# LCD_Glass_Ext_connector.net
KiCad netlist of a schematic drawn in Altium Designer
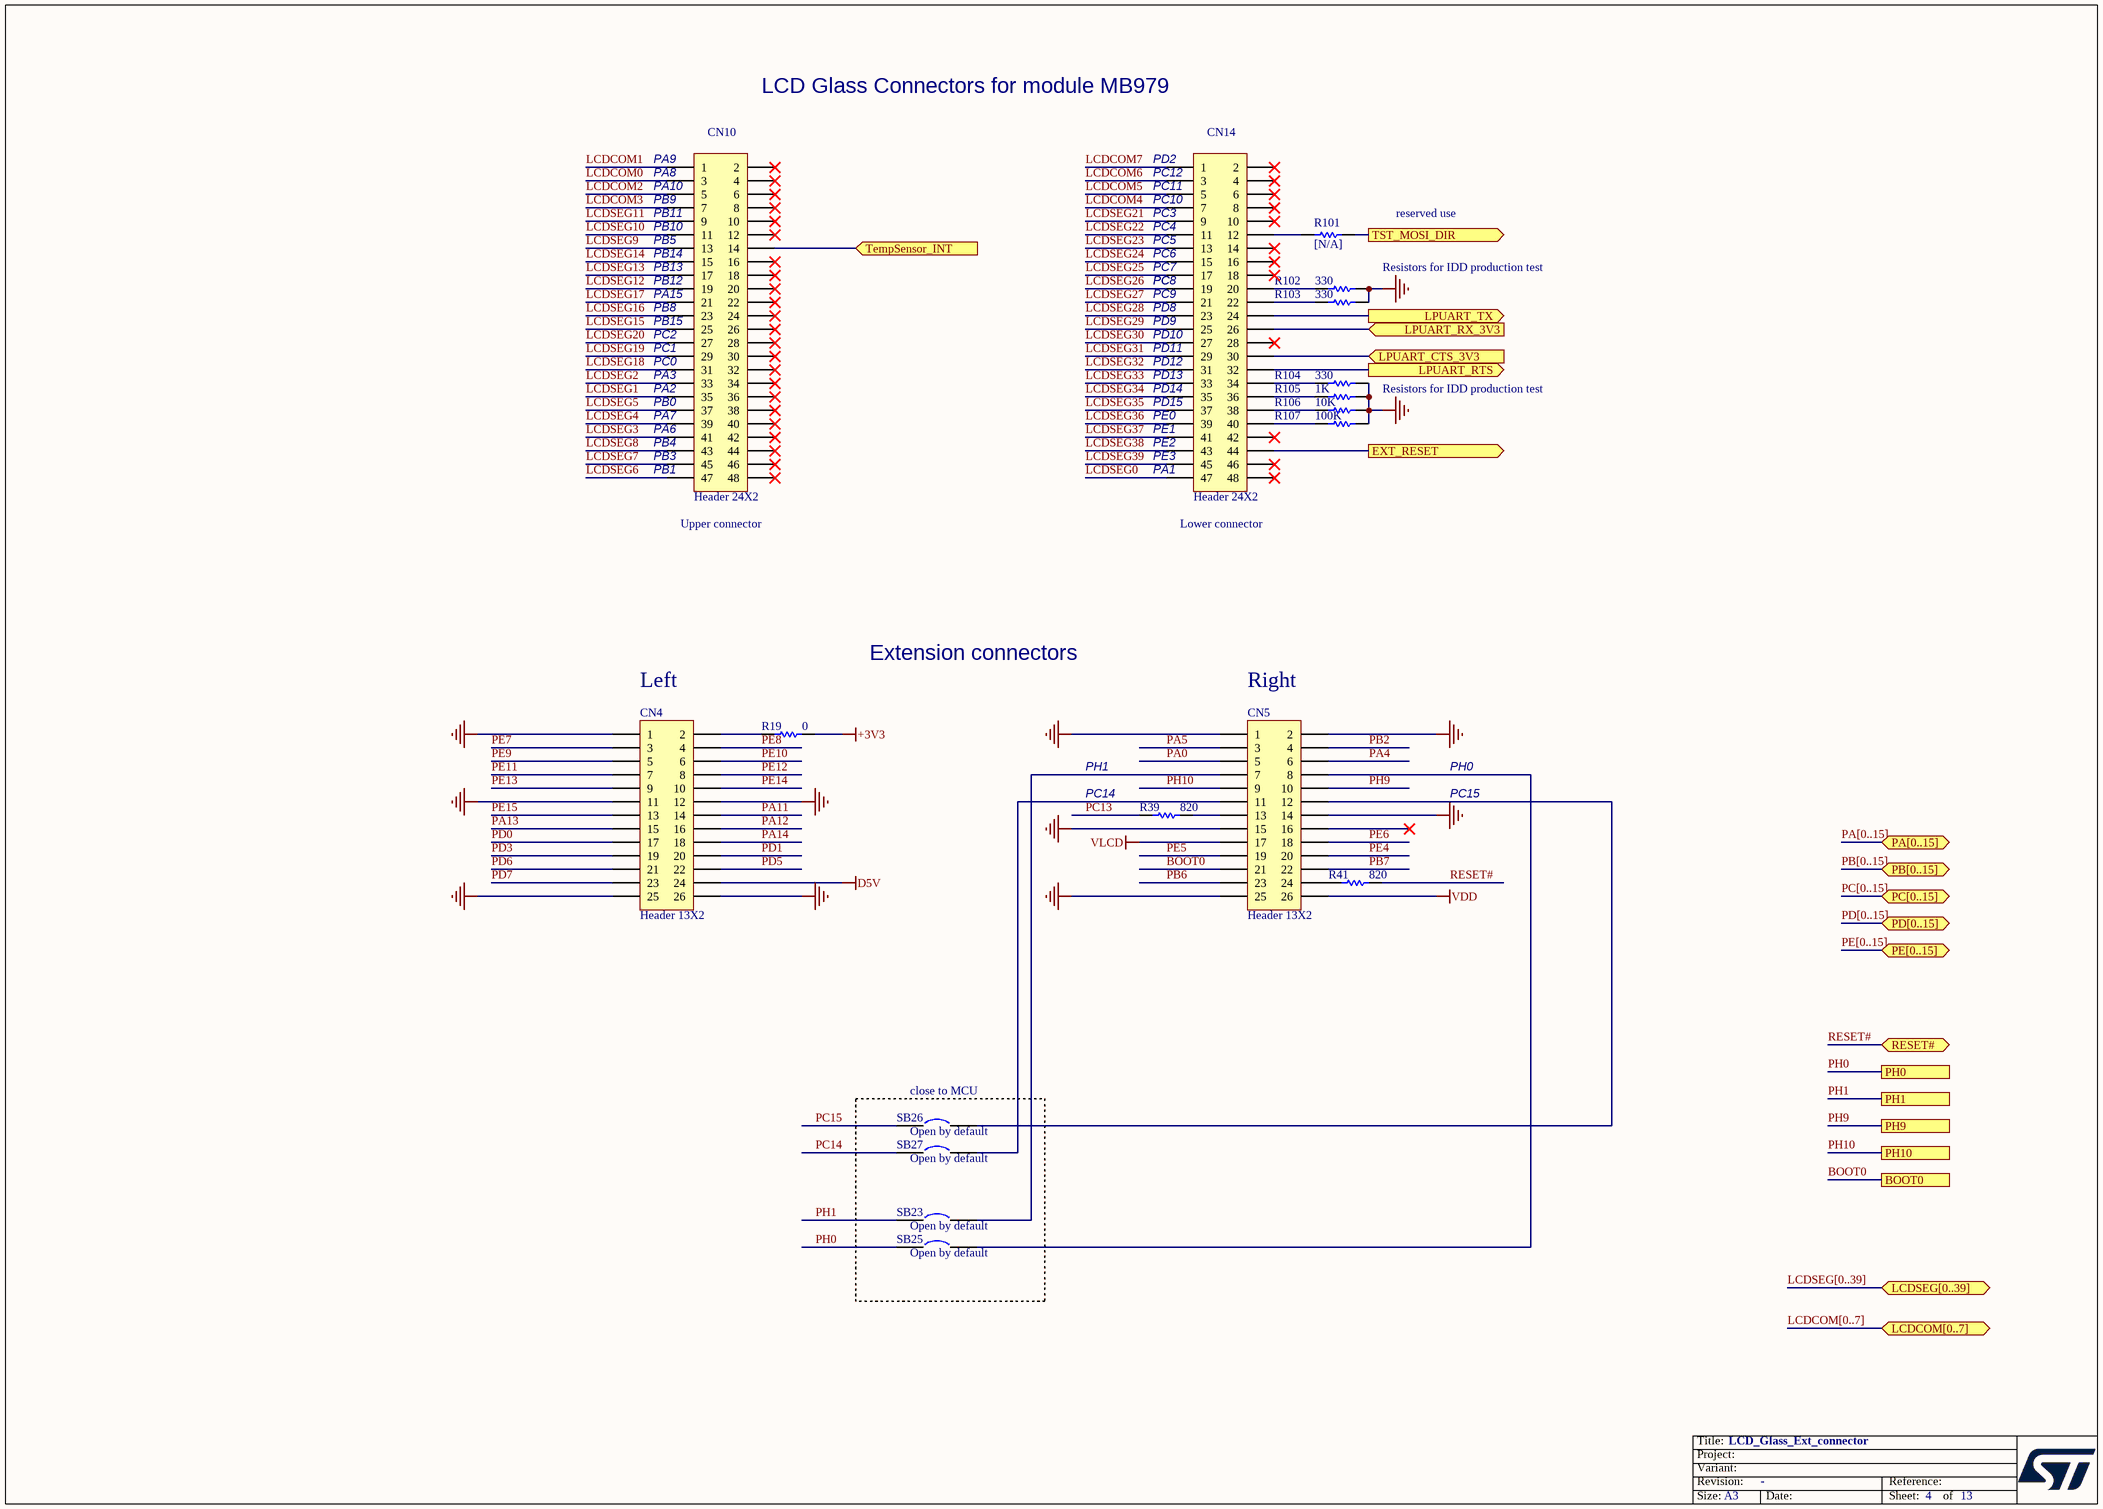
[diagram p0: LCD_Glass_Ext_connector.SchDoc]

(export (version "E")
  (design (tool "Eeschema 10.0.6"))
  (components
    (comp (ref "CN4")
      (value "Header 13X2")
      (footprint "HDR_2X13_2R54")
      (description "Header, 13-Pin, Dual row")
      (fields (field (name "PUBLISHER") "Altium Limited"))
      (libsource (lib "Miscellaneous Connectors") (part "Header 13X2"))
    )
    (comp (ref "CN5")
      (value "Header 13X2")
      (footprint "HDR_2X13_2R54")
      (description "Header, 13-Pin, Dual row")
      (fields (field (name "PUBLISHER") "Altium Limited"))
      (libsource (lib "Miscellaneous Connectors") (part "Header 13X2"))
    )
    (comp (ref "CN10")
      (value "Header 24X2")
      (footprint "HDR_2X24_2R54")
      (description "Header, 24-Pin, Dual row")
      (fields (field (name "PUBLISHER") "Altium Limited"))
      (libsource (lib "Miscellaneous Connectors") (part "Header 24X2"))
    )
    (comp (ref "CN14")
      (value "Header 24X2")
      (footprint "HDR_2X24_2R54")
      (description "Header, 24-Pin, Dual row")
      (fields (field (name "PUBLISHER") "Altium Limited"))
      (libsource (lib "Miscellaneous Connectors") (part "Header 24X2"))
    )
    (comp (ref "R19")
      (value "0")
      (footprint "0603R")
      (description "Resistor")
      (fields (field (name "PUBLISHER") "Altium Limited"))
      (libsource (lib "Miscellaneous Devices") (part "Res1"))
    )
    (comp (ref "R39")
      (value "820")
      (footprint "0603R")
      (description "Resistor")
      (fields (field (name "PUBLISHER") "Altium Limited"))
      (libsource (lib "Miscellaneous Devices") (part "Res1"))
    )
    (comp (ref "R41")
      (value "820")
      (footprint "0603R")
      (description "Resistor")
      (fields (field (name "PUBLISHER") "Altium Limited"))
      (libsource (lib "Miscellaneous Devices") (part "Res1"))
    )
    (comp (ref "R101")
      (value "[N/A]")
      (footprint "0603R")
      (description "Resistor")
      (fields (field (name "PUBLISHER") "Altium Limited"))
      (libsource (lib "Miscellaneous Devices") (part "res1"))
    )
    (comp (ref "R102")
      (value "330")
      (footprint "0603R")
      (description "Resistor")
      (fields (field (name "PUBLISHER") "Altium Limited"))
      (libsource (lib "Miscellaneous Devices") (part "res1"))
    )
    (comp (ref "R103")
      (value "330")
      (footprint "0603R")
      (description "Resistor")
      (fields (field (name "PUBLISHER") "Altium Limited"))
      (libsource (lib "Miscellaneous Devices") (part "res1"))
    )
    (comp (ref "R104")
      (value "330")
      (footprint "0603R")
      (description "Resistor")
      (fields (field (name "PUBLISHER") "Altium Limited"))
      (libsource (lib "Miscellaneous Devices") (part "res1"))
    )
    (comp (ref "R105")
      (value "1K")
      (footprint "0402R")
      (description "Resistor")
      (fields (field (name "PUBLISHER") "Altium Limited"))
      (libsource (lib "Miscellaneous Devices") (part "Res1"))
    )
    (comp (ref "R106")
      (value "10K")
      (footprint "0603R")
      (description "Resistor")
      (fields (field (name "PUBLISHER") "Altium Limited"))
      (libsource (lib "Miscellaneous Devices") (part "res1"))
    )
    (comp (ref "R107")
      (value "100K")
      (footprint "0603R")
      (description "Resistor")
      (fields (field (name "PUBLISHER") "Altium Limited"))
      (libsource (lib "Miscellaneous Devices") (part "res1"))
    )
    (comp (ref "SB23")
      (value "Open by default")
      (footprint "SB_0603")
      (description "Circuit Breaker")
      (fields (field (name "PUBLISHER") "Altium Limited"))
      (libsource (lib "Miscellaneous Devices") (part "Circuit Breaker"))
    )
    (comp (ref "SB25")
      (value "Open by default")
      (footprint "SB_0603")
      (description "Circuit Breaker")
      (fields (field (name "PUBLISHER") "Altium Limited"))
      (libsource (lib "Miscellaneous Devices") (part "Circuit Breaker"))
    )
    (comp (ref "SB26")
      (value "Open by default")
      (footprint "SB_0603")
      (description "Circuit Breaker")
      (fields (field (name "PUBLISHER") "Altium Limited"))
      (libsource (lib "Miscellaneous Devices") (part "Circuit Breaker"))
    )
    (comp (ref "SB27")
      (value "Open by default")
      (footprint "SB_0603")
      (description "Circuit Breaker")
      (fields (field (name "PUBLISHER") "Altium Limited"))
      (libsource (lib "Miscellaneous Devices") (part "Circuit Breaker"))
    )
  )
  (nets
    (net (code "50") (name "+3V3") (class "Default")
      (node (ref "R19") (pin "1") (pinfunction "1_1") (pintype "passive"))
    )
    (net (code "51") (name "/BOOT0") (class "Default")
      (node (ref "CN5") (pin "21") (pinfunction "21_21") (pintype "passive"))
    )
    (net (code "52") (name "/EXT_RESET") (class "Default")
      (node (ref "CN14") (pin "44") (pinfunction "44_44") (pintype "passive"))
    )
    (net (code "53") (name "/LCDCOM0") (class "Default")
      (node (ref "CN10") (pin "3") (pinfunction "3_3") (pintype "passive"))
    )
    (net (code "54") (name "/LCDCOM1") (class "Default")
      (node (ref "CN10") (pin "1") (pinfunction "1_1") (pintype "passive"))
    )
    (net (code "55") (name "/LCDCOM2") (class "Default")
      (node (ref "CN10") (pin "5") (pinfunction "5_5") (pintype "passive"))
    )
    (net (code "56") (name "/LCDCOM3") (class "Default")
      (node (ref "CN10") (pin "7") (pinfunction "7_7") (pintype "passive"))
    )
    (net (code "57") (name "/LCDCOM4") (class "Default")
      (node (ref "CN14") (pin "7") (pinfunction "7_7") (pintype "passive"))
    )
    (net (code "58") (name "/LCDCOM5") (class "Default")
      (node (ref "CN14") (pin "5") (pinfunction "5_5") (pintype "passive"))
    )
    (net (code "59") (name "/LCDCOM6") (class "Default")
      (node (ref "CN14") (pin "3") (pinfunction "3_3") (pintype "passive"))
    )
    (net (code "60") (name "/LCDCOM7") (class "Default")
      (node (ref "CN14") (pin "1") (pinfunction "1_1") (pintype "passive"))
    )
    (net (code "62") (name "/LCDSEG0") (class "Default")
      (node (ref "CN14") (pin "47") (pinfunction "47_47") (pintype "passive"))
    )
    (net (code "63") (name "/LCDSEG1") (class "Default")
      (node (ref "CN10") (pin "35") (pinfunction "35_35") (pintype "passive"))
    )
    (net (code "64") (name "/LCDSEG2") (class "Default")
      (node (ref "CN10") (pin "33") (pinfunction "33_33") (pintype "passive"))
    )
    (net (code "65") (name "/LCDSEG3") (class "Default")
      (node (ref "CN10") (pin "41") (pinfunction "41_41") (pintype "passive"))
    )
    (net (code "66") (name "/LCDSEG4") (class "Default")
      (node (ref "CN10") (pin "39") (pinfunction "39_39") (pintype "passive"))
    )
    (net (code "67") (name "/LCDSEG5") (class "Default")
      (node (ref "CN10") (pin "37") (pinfunction "37_37") (pintype "passive"))
    )
    (net (code "68") (name "/LCDSEG6") (class "Default")
      (node (ref "CN10") (pin "47") (pinfunction "47_47") (pintype "passive"))
    )
    (net (code "69") (name "/LCDSEG7") (class "Default")
      (node (ref "CN10") (pin "45") (pinfunction "45_45") (pintype "passive"))
    )
    (net (code "70") (name "/LCDSEG8") (class "Default")
      (node (ref "CN10") (pin "43") (pinfunction "43_43") (pintype "passive"))
    )
    (net (code "71") (name "/LCDSEG9") (class "Default")
      (node (ref "CN10") (pin "13") (pinfunction "13_13") (pintype "passive"))
    )
    (net (code "72") (name "/LCDSEG10") (class "Default")
      (node (ref "CN10") (pin "11") (pinfunction "11_11") (pintype "passive"))
    )
    (net (code "73") (name "/LCDSEG11") (class "Default")
      (node (ref "CN10") (pin "9") (pinfunction "9_9") (pintype "passive"))
    )
    (net (code "74") (name "/LCDSEG12") (class "Default")
      (node (ref "CN10") (pin "19") (pinfunction "19_19") (pintype "passive"))
    )
    (net (code "75") (name "/LCDSEG13") (class "Default")
      (node (ref "CN10") (pin "17") (pinfunction "17_17") (pintype "passive"))
    )
    (net (code "76") (name "/LCDSEG14") (class "Default")
      (node (ref "CN10") (pin "15") (pinfunction "15_15") (pintype "passive"))
    )
    (net (code "77") (name "/LCDSEG15") (class "Default")
      (node (ref "CN10") (pin "25") (pinfunction "25_25") (pintype "passive"))
    )
    (net (code "78") (name "/LCDSEG16") (class "Default")
      (node (ref "CN10") (pin "23") (pinfunction "23_23") (pintype "passive"))
    )
    (net (code "79") (name "/LCDSEG17") (class "Default")
      (node (ref "CN10") (pin "21") (pinfunction "21_21") (pintype "passive"))
    )
    (net (code "80") (name "/LCDSEG18") (class "Default")
      (node (ref "CN10") (pin "31") (pinfunction "31_31") (pintype "passive"))
    )
    (net (code "81") (name "/LCDSEG19") (class "Default")
      (node (ref "CN10") (pin "29") (pinfunction "29_29") (pintype "passive"))
    )
    (net (code "82") (name "/LCDSEG20") (class "Default")
      (node (ref "CN10") (pin "27") (pinfunction "27_27") (pintype "passive"))
    )
    (net (code "83") (name "/LCDSEG21") (class "Default")
      (node (ref "CN14") (pin "9") (pinfunction "9_9") (pintype "passive"))
    )
    (net (code "84") (name "/LCDSEG22") (class "Default")
      (node (ref "CN14") (pin "11") (pinfunction "11_11") (pintype "passive"))
    )
    (net (code "85") (name "/LCDSEG23") (class "Default")
      (node (ref "CN14") (pin "13") (pinfunction "13_13") (pintype "passive"))
    )
    (net (code "86") (name "/LCDSEG24") (class "Default")
      (node (ref "CN14") (pin "15") (pinfunction "15_15") (pintype "passive"))
    )
    (net (code "87") (name "/LCDSEG25") (class "Default")
      (node (ref "CN14") (pin "17") (pinfunction "17_17") (pintype "passive"))
    )
    (net (code "88") (name "/LCDSEG26") (class "Default")
      (node (ref "CN14") (pin "19") (pinfunction "19_19") (pintype "passive"))
    )
    (net (code "89") (name "/LCDSEG27") (class "Default")
      (node (ref "CN14") (pin "21") (pinfunction "21_21") (pintype "passive"))
    )
    (net (code "90") (name "/LCDSEG28") (class "Default")
      (node (ref "CN14") (pin "23") (pinfunction "23_23") (pintype "passive"))
    )
    (net (code "91") (name "/LCDSEG29") (class "Default")
      (node (ref "CN14") (pin "25") (pinfunction "25_25") (pintype "passive"))
    )
    (net (code "92") (name "/LCDSEG30") (class "Default")
      (node (ref "CN14") (pin "27") (pinfunction "27_27") (pintype "passive"))
    )
    (net (code "93") (name "/LCDSEG31") (class "Default")
      (node (ref "CN14") (pin "29") (pinfunction "29_29") (pintype "passive"))
    )
    (net (code "94") (name "/LCDSEG32") (class "Default")
      (node (ref "CN14") (pin "31") (pinfunction "31_31") (pintype "passive"))
    )
    (net (code "95") (name "/LCDSEG33") (class "Default")
      (node (ref "CN14") (pin "33") (pinfunction "33_33") (pintype "passive"))
    )
    (net (code "96") (name "/LCDSEG34") (class "Default")
      (node (ref "CN14") (pin "35") (pinfunction "35_35") (pintype "passive"))
    )
    (net (code "97") (name "/LCDSEG35") (class "Default")
      (node (ref "CN14") (pin "37") (pinfunction "37_37") (pintype "passive"))
    )
    (net (code "98") (name "/LCDSEG36") (class "Default")
      (node (ref "CN14") (pin "39") (pinfunction "39_39") (pintype "passive"))
    )
    (net (code "99") (name "/LCDSEG37") (class "Default")
      (node (ref "CN14") (pin "41") (pinfunction "41_41") (pintype "passive"))
    )
    (net (code "100") (name "/LCDSEG38") (class "Default")
      (node (ref "CN14") (pin "43") (pinfunction "43_43") (pintype "passive"))
    )
    (net (code "101") (name "/LCDSEG39") (class "Default")
      (node (ref "CN14") (pin "45") (pinfunction "45_45") (pintype "passive"))
    )
    (net (code "103") (name "/LPUART_CTS_3V3") (class "Default")
      (node (ref "CN14") (pin "30") (pinfunction "30_30") (pintype "passive"))
    )
    (net (code "104") (name "/LPUART_RTS") (class "Default")
      (node (ref "CN14") (pin "32") (pinfunction "32_32") (pintype "passive"))
    )
    (net (code "105") (name "/LPUART_RX_3V3") (class "Default")
      (node (ref "CN14") (pin "26") (pinfunction "26_26") (pintype "passive"))
    )
    (net (code "106") (name "/LPUART_TX") (class "Default")
      (node (ref "CN14") (pin "24") (pinfunction "24_24") (pintype "passive"))
    )
    (net (code "107") (name "/PA0") (class "Default")
      (node (ref "CN5") (pin "5") (pinfunction "5_5") (pintype "passive"))
    )
    (net (code "108") (name "/PA4") (class "Default")
      (node (ref "CN5") (pin "6") (pinfunction "6_6") (pintype "passive"))
    )
    (net (code "109") (name "/PA5") (class "Default")
      (node (ref "CN5") (pin "3") (pinfunction "3_3") (pintype "passive"))
    )
    (net (code "110") (name "/PA11") (class "Default")
      (node (ref "CN4") (pin "14") (pinfunction "14_14") (pintype "passive"))
    )
    (net (code "111") (name "/PA12") (class "Default")
      (node (ref "CN4") (pin "16") (pinfunction "16_16") (pintype "passive"))
    )
    (net (code "112") (name "/PA13") (class "Default")
      (node (ref "CN4") (pin "15") (pinfunction "15_15") (pintype "passive"))
    )
    (net (code "113") (name "/PA14") (class "Default")
      (node (ref "CN4") (pin "18") (pinfunction "18_18") (pintype "passive"))
    )
    (net (code "115") (name "/PB2") (class "Default")
      (node (ref "CN5") (pin "4") (pinfunction "4_4") (pintype "passive"))
    )
    (net (code "116") (name "/PB6") (class "Default")
      (node (ref "CN5") (pin "23") (pinfunction "23_23") (pintype "passive"))
    )
    (net (code "117") (name "/PB7") (class "Default")
      (node (ref "CN5") (pin "22") (pinfunction "22_22") (pintype "passive"))
    )
    (net (code "119") (name "/PC13") (class "Default")
      (node (ref "R39") (pin "1") (pinfunction "1_1") (pintype "passive"))
    )
    (net (code "120") (name "/PC14") (class "Default")
      (node (ref "SB27") (pin "1") (pinfunction "1_1") (pintype "passive"))
    )
    (net (code "121") (name "/PC15") (class "Default")
      (node (ref "SB26") (pin "1") (pinfunction "1_1") (pintype "passive"))
    )
    (net (code "123") (name "/PD0") (class "Default")
      (node (ref "CN4") (pin "17") (pinfunction "17_17") (pintype "passive"))
    )
    (net (code "124") (name "/PD1") (class "Default")
      (node (ref "CN4") (pin "20") (pinfunction "20_20") (pintype "passive"))
    )
    (net (code "125") (name "/PD3") (class "Default")
      (node (ref "CN4") (pin "19") (pinfunction "19_19") (pintype "passive"))
    )
    (net (code "126") (name "/PD5") (class "Default")
      (node (ref "CN4") (pin "22") (pinfunction "22_22") (pintype "passive"))
    )
    (net (code "127") (name "/PD6") (class "Default")
      (node (ref "CN4") (pin "21") (pinfunction "21_21") (pintype "passive"))
    )
    (net (code "128") (name "/PD7") (class "Default")
      (node (ref "CN4") (pin "23") (pinfunction "23_23") (pintype "passive"))
    )
    (net (code "130") (name "/PE4") (class "Default")
      (node (ref "CN5") (pin "20") (pinfunction "20_20") (pintype "passive"))
    )
    (net (code "131") (name "/PE5") (class "Default")
      (node (ref "CN5") (pin "19") (pinfunction "19_19") (pintype "passive"))
    )
    (net (code "132") (name "/PE6") (class "Default")
      (node (ref "CN5") (pin "18") (pinfunction "18_18") (pintype "passive"))
    )
    (net (code "133") (name "/PE7") (class "Default")
      (node (ref "CN4") (pin "3") (pinfunction "3_3") (pintype "passive"))
    )
    (net (code "134") (name "/PE8") (class "Default")
      (node (ref "CN4") (pin "4") (pinfunction "4_4") (pintype "passive"))
    )
    (net (code "135") (name "/PE9") (class "Default")
      (node (ref "CN4") (pin "5") (pinfunction "5_5") (pintype "passive"))
    )
    (net (code "136") (name "/PE10") (class "Default")
      (node (ref "CN4") (pin "6") (pinfunction "6_6") (pintype "passive"))
    )
    (net (code "137") (name "/PE11") (class "Default")
      (node (ref "CN4") (pin "7") (pinfunction "7_7") (pintype "passive"))
    )
    (net (code "138") (name "/PE12") (class "Default")
      (node (ref "CN4") (pin "8") (pinfunction "8_8") (pintype "passive"))
    )
    (net (code "139") (name "/PE13") (class "Default")
      (node (ref "CN4") (pin "9") (pinfunction "9_9") (pintype "passive"))
    )
    (net (code "140") (name "/PE14") (class "Default")
      (node (ref "CN4") (pin "10") (pinfunction "10_10") (pintype "passive"))
    )
    (net (code "141") (name "/PE15") (class "Default")
      (node (ref "CN4") (pin "13") (pinfunction "13_13") (pintype "passive"))
    )
    (net (code "143") (name "/PH0") (class "Default")
      (node (ref "SB25") (pin "1") (pinfunction "1_1") (pintype "passive"))
    )
    (net (code "144") (name "/PH1") (class "Default")
      (node (ref "SB23") (pin "1") (pinfunction "1_1") (pintype "passive"))
    )
    (net (code "145") (name "/PH9") (class "Default")
      (node (ref "CN5") (pin "10") (pinfunction "10_10") (pintype "passive"))
    )
    (net (code "146") (name "/PH10") (class "Default")
      (node (ref "CN5") (pin "9") (pinfunction "9_9") (pintype "passive"))
    )
    (net (code "147") (name "/RESET#") (class "Default")
      (node (ref "R41") (pin "1") (pinfunction "1_1") (pintype "passive"))
    )
    (net (code "148") (name "/TST_MOSI_DIR") (class "Default")
      (node (ref "R101") (pin "1") (pinfunction "1_1") (pintype "passive"))
    )
    (net (code "149") (name "/TempSensor_INT") (class "Default")
      (node (ref "CN10") (pin "14") (pinfunction "14_14") (pintype "passive"))
    )
    (net (code "150") (name "D5V") (class "Default")
      (node (ref "CN4") (pin "24") (pinfunction "24_24") (pintype "passive"))
    )
    (net (code "151") (name "GND") (class "Default")
      (node (ref "CN4") (pin "1") (pinfunction "1_1") (pintype "passive"))
      (node (ref "CN4") (pin "11") (pinfunction "11_11") (pintype "passive"))
      (node (ref "CN4") (pin "12") (pinfunction "12_12") (pintype "passive"))
      (node (ref "CN4") (pin "25") (pinfunction "25_25") (pintype "passive"))
      (node (ref "CN4") (pin "26") (pinfunction "26_26") (pintype "passive"))
      (node (ref "CN5") (pin "1") (pinfunction "1_1") (pintype "passive"))
      (node (ref "CN5") (pin "14") (pinfunction "14_14") (pintype "passive"))
      (node (ref "CN5") (pin "15") (pinfunction "15_15") (pintype "passive"))
      (node (ref "CN5") (pin "2") (pinfunction "2_2") (pintype "passive"))
      (node (ref "CN5") (pin "25") (pinfunction "25_25") (pintype "passive"))
      (node (ref "R102") (pin "1") (pinfunction "1_1") (pintype "passive"))
      (node (ref "R103") (pin "1") (pinfunction "1_1") (pintype "passive"))
      (node (ref "R104") (pin "1") (pinfunction "1_1") (pintype "passive"))
      (node (ref "R105") (pin "2") (pinfunction "2_2") (pintype "passive"))
      (node (ref "R106") (pin "1") (pinfunction "1_1") (pintype "passive"))
      (node (ref "R107") (pin "1") (pinfunction "1_1") (pintype "passive"))
    )
    (net (code "152") (name "Net-(CN4-Pad2)") (class "Default")
      (node (ref "CN4") (pin "2") (pinfunction "2_2") (pintype "passive"))
      (node (ref "R19") (pin "2") (pinfunction "2_2") (pintype "passive"))
    )
    (net (code "153") (name "Net-(CN5-Pad7)") (class "Default")
      (node (ref "CN5") (pin "7") (pinfunction "7_7") (pintype "passive"))
      (node (ref "SB23") (pin "2") (pinfunction "2_2") (pintype "passive"))
    )
    (net (code "154") (name "Net-(CN5-Pad8)") (class "Default")
      (node (ref "CN5") (pin "8") (pinfunction "8_8") (pintype "passive"))
      (node (ref "SB25") (pin "2") (pinfunction "2_2") (pintype "passive"))
    )
    (net (code "155") (name "Net-(CN5-Pad11)") (class "Default")
      (node (ref "CN5") (pin "11") (pinfunction "11_11") (pintype "passive"))
      (node (ref "SB27") (pin "2") (pinfunction "2_2") (pintype "passive"))
    )
    (net (code "156") (name "Net-(CN5-Pad12)") (class "Default")
      (node (ref "CN5") (pin "12") (pinfunction "12_12") (pintype "passive"))
      (node (ref "SB26") (pin "2") (pinfunction "2_2") (pintype "passive"))
    )
    (net (code "157") (name "Net-(CN5-Pad13)") (class "Default")
      (node (ref "CN5") (pin "13") (pinfunction "13_13") (pintype "passive"))
      (node (ref "R39") (pin "2") (pinfunction "2_2") (pintype "passive"))
    )
    (net (code "158") (name "Net-(CN5-Pad24)") (class "Default")
      (node (ref "CN5") (pin "24") (pinfunction "24_24") (pintype "passive"))
      (node (ref "R41") (pin "2") (pinfunction "2_2") (pintype "passive"))
    )
    (net (code "159") (name "Net-(CN14-Pad12)") (class "Default")
      (node (ref "CN14") (pin "12") (pinfunction "12_12") (pintype "passive"))
      (node (ref "R101") (pin "2") (pinfunction "2_2") (pintype "passive"))
    )
    (net (code "160") (name "Net-(CN14-Pad20)") (class "Default")
      (node (ref "CN14") (pin "20") (pinfunction "20_20") (pintype "passive"))
      (node (ref "R102") (pin "2") (pinfunction "2_2") (pintype "passive"))
    )
    (net (code "161") (name "Net-(CN14-Pad22)") (class "Default")
      (node (ref "CN14") (pin "22") (pinfunction "22_22") (pintype "passive"))
      (node (ref "R103") (pin "2") (pinfunction "2_2") (pintype "passive"))
    )
    (net (code "162") (name "Net-(CN14-Pad34)") (class "Default")
      (node (ref "CN14") (pin "34") (pinfunction "34_34") (pintype "passive"))
      (node (ref "R104") (pin "2") (pinfunction "2_2") (pintype "passive"))
    )
    (net (code "163") (name "Net-(CN14-Pad36)") (class "Default")
      (node (ref "CN14") (pin "36") (pinfunction "36_36") (pintype "passive"))
      (node (ref "R105") (pin "1") (pinfunction "1_1") (pintype "passive"))
    )
    (net (code "164") (name "Net-(CN14-Pad38)") (class "Default")
      (node (ref "CN14") (pin "38") (pinfunction "38_38") (pintype "passive"))
      (node (ref "R106") (pin "2") (pinfunction "2_2") (pintype "passive"))
    )
    (net (code "165") (name "Net-(CN14-Pad40)") (class "Default")
      (node (ref "CN14") (pin "40") (pinfunction "40_40") (pintype "passive"))
      (node (ref "R107") (pin "2") (pinfunction "2_2") (pintype "passive"))
    )
    (net (code "166") (name "VDD") (class "Default")
      (node (ref "CN5") (pin "26") (pinfunction "26_26") (pintype "passive"))
    )
    (net (code "167") (name "VLCD") (class "Default")
      (node (ref "CN5") (pin "17") (pinfunction "17_17") (pintype "passive"))
    )
    (net (code "168") (name "unconnected-(CN5-Pad16)") (class "Default")
      (node (ref "CN5") (pin "16") (pinfunction "16_16") (pintype "passive+no_connect"))
    )
    (net (code "169") (name "unconnected-(CN10-Pad2)") (class "Default")
      (node (ref "CN10") (pin "2") (pinfunction "2_2") (pintype "passive+no_connect"))
    )
    (net (code "170") (name "unconnected-(CN10-Pad4)") (class "Default")
      (node (ref "CN10") (pin "4") (pinfunction "4_4") (pintype "passive+no_connect"))
    )
    (net (code "171") (name "unconnected-(CN10-Pad6)") (class "Default")
      (node (ref "CN10") (pin "6") (pinfunction "6_6") (pintype "passive+no_connect"))
    )
    (net (code "172") (name "unconnected-(CN10-Pad8)") (class "Default")
      (node (ref "CN10") (pin "8") (pinfunction "8_8") (pintype "passive+no_connect"))
    )
    (net (code "173") (name "unconnected-(CN10-Pad10)") (class "Default")
      (node (ref "CN10") (pin "10") (pinfunction "10_10") (pintype "passive+no_connect"))
    )
    (net (code "174") (name "unconnected-(CN10-Pad12)") (class "Default")
      (node (ref "CN10") (pin "12") (pinfunction "12_12") (pintype "passive+no_connect"))
    )
    (net (code "175") (name "unconnected-(CN10-Pad16)") (class "Default")
      (node (ref "CN10") (pin "16") (pinfunction "16_16") (pintype "passive+no_connect"))
    )
    (net (code "176") (name "unconnected-(CN10-Pad18)") (class "Default")
      (node (ref "CN10") (pin "18") (pinfunction "18_18") (pintype "passive+no_connect"))
    )
    (net (code "177") (name "unconnected-(CN10-Pad20)") (class "Default")
      (node (ref "CN10") (pin "20") (pinfunction "20_20") (pintype "passive+no_connect"))
    )
    (net (code "178") (name "unconnected-(CN10-Pad22)") (class "Default")
      (node (ref "CN10") (pin "22") (pinfunction "22_22") (pintype "passive+no_connect"))
    )
    (net (code "179") (name "unconnected-(CN10-Pad24)") (class "Default")
      (node (ref "CN10") (pin "24") (pinfunction "24_24") (pintype "passive+no_connect"))
    )
    (net (code "180") (name "unconnected-(CN10-Pad26)") (class "Default")
      (node (ref "CN10") (pin "26") (pinfunction "26_26") (pintype "passive+no_connect"))
    )
    (net (code "181") (name "unconnected-(CN10-Pad28)") (class "Default")
      (node (ref "CN10") (pin "28") (pinfunction "28_28") (pintype "passive+no_connect"))
    )
    (net (code "182") (name "unconnected-(CN10-Pad30)") (class "Default")
      (node (ref "CN10") (pin "30") (pinfunction "30_30") (pintype "passive+no_connect"))
    )
    (net (code "183") (name "unconnected-(CN10-Pad32)") (class "Default")
      (node (ref "CN10") (pin "32") (pinfunction "32_32") (pintype "passive+no_connect"))
    )
    (net (code "184") (name "unconnected-(CN10-Pad34)") (class "Default")
      (node (ref "CN10") (pin "34") (pinfunction "34_34") (pintype "passive+no_connect"))
    )
    (net (code "185") (name "unconnected-(CN10-Pad36)") (class "Default")
      (node (ref "CN10") (pin "36") (pinfunction "36_36") (pintype "passive+no_connect"))
    )
    (net (code "186") (name "unconnected-(CN10-Pad38)") (class "Default")
      (node (ref "CN10") (pin "38") (pinfunction "38_38") (pintype "passive+no_connect"))
    )
    (net (code "187") (name "unconnected-(CN10-Pad40)") (class "Default")
      (node (ref "CN10") (pin "40") (pinfunction "40_40") (pintype "passive+no_connect"))
    )
    (net (code "188") (name "unconnected-(CN10-Pad42)") (class "Default")
      (node (ref "CN10") (pin "42") (pinfunction "42_42") (pintype "passive+no_connect"))
    )
    (net (code "189") (name "unconnected-(CN10-Pad44)") (class "Default")
      (node (ref "CN10") (pin "44") (pinfunction "44_44") (pintype "passive+no_connect"))
    )
    (net (code "190") (name "unconnected-(CN10-Pad46)") (class "Default")
      (node (ref "CN10") (pin "46") (pinfunction "46_46") (pintype "passive+no_connect"))
    )
    (net (code "191") (name "unconnected-(CN10-Pad48)") (class "Default")
      (node (ref "CN10") (pin "48") (pinfunction "48_48") (pintype "passive+no_connect"))
    )
    (net (code "192") (name "unconnected-(CN14-Pad2)") (class "Default")
      (node (ref "CN14") (pin "2") (pinfunction "2_2") (pintype "passive+no_connect"))
    )
    (net (code "193") (name "unconnected-(CN14-Pad4)") (class "Default")
      (node (ref "CN14") (pin "4") (pinfunction "4_4") (pintype "passive+no_connect"))
    )
    (net (code "194") (name "unconnected-(CN14-Pad6)") (class "Default")
      (node (ref "CN14") (pin "6") (pinfunction "6_6") (pintype "passive+no_connect"))
    )
    (net (code "195") (name "unconnected-(CN14-Pad8)") (class "Default")
      (node (ref "CN14") (pin "8") (pinfunction "8_8") (pintype "passive+no_connect"))
    )
    (net (code "196") (name "unconnected-(CN14-Pad10)") (class "Default")
      (node (ref "CN14") (pin "10") (pinfunction "10_10") (pintype "passive+no_connect"))
    )
    (net (code "197") (name "unconnected-(CN14-Pad14)") (class "Default")
      (node (ref "CN14") (pin "14") (pinfunction "14_14") (pintype "passive+no_connect"))
    )
    (net (code "198") (name "unconnected-(CN14-Pad16)") (class "Default")
      (node (ref "CN14") (pin "16") (pinfunction "16_16") (pintype "passive+no_connect"))
    )
    (net (code "199") (name "unconnected-(CN14-Pad18)") (class "Default")
      (node (ref "CN14") (pin "18") (pinfunction "18_18") (pintype "passive+no_connect"))
    )
    (net (code "200") (name "unconnected-(CN14-Pad28)") (class "Default")
      (node (ref "CN14") (pin "28") (pinfunction "28_28") (pintype "passive+no_connect"))
    )
    (net (code "201") (name "unconnected-(CN14-Pad42)") (class "Default")
      (node (ref "CN14") (pin "42") (pinfunction "42_42") (pintype "passive+no_connect"))
    )
    (net (code "202") (name "unconnected-(CN14-Pad46)") (class "Default")
      (node (ref "CN14") (pin "46") (pinfunction "46_46") (pintype "passive+no_connect"))
    )
    (net (code "203") (name "unconnected-(CN14-Pad48)") (class "Default")
      (node (ref "CN14") (pin "48") (pinfunction "48_48") (pintype "passive+no_connect"))
    )
  )
)
